# RGBDisplayDriver.net
KiCad netlist of a schematic drawn in EAGLE
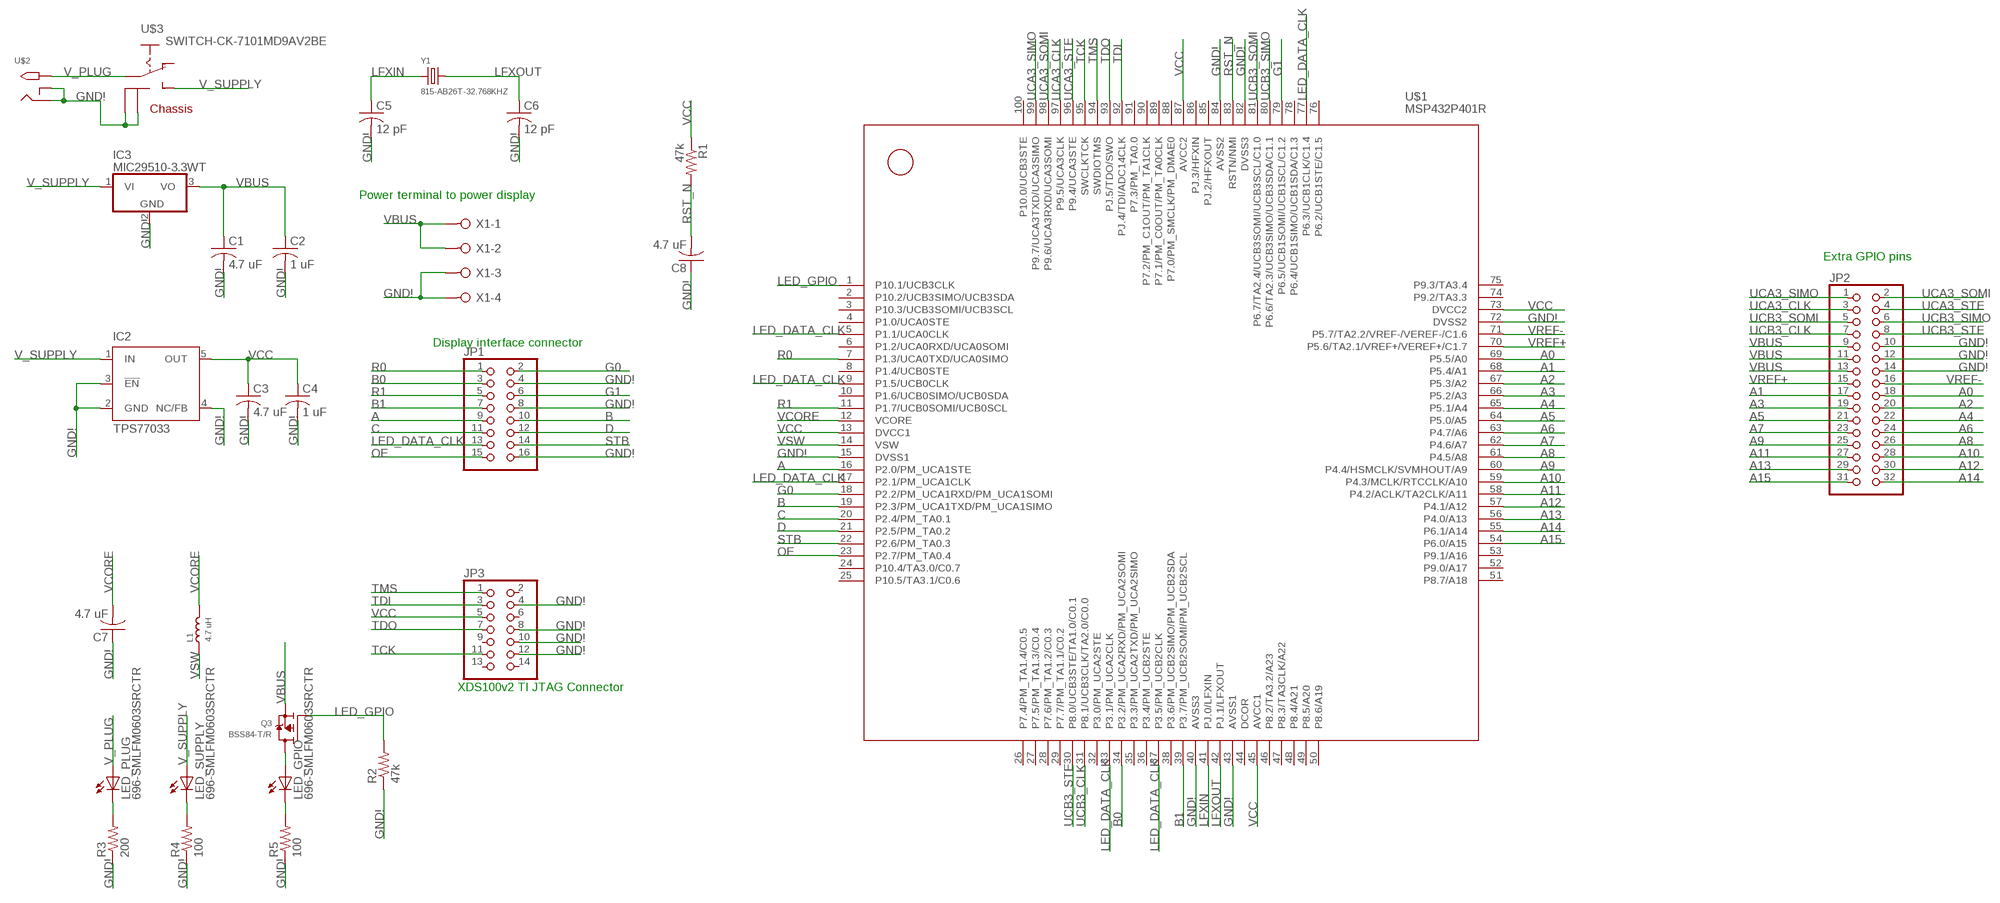
[diagram p0: schematic, sheet 1]

(export (version "E")
  (design (tool "Eeschema 10.0.6"))
  (components
    (comp (ref "C1")
      (value "4.7 uF")
      (footprint "eagle-import:C0603")
      (libsource (lib "eagle-import") (part "C-USC0603"))
    )
    (comp (ref "C2")
      (value "1 uF")
      (footprint "eagle-import:C0603")
      (libsource (lib "eagle-import") (part "C-USC0603"))
    )
    (comp (ref "C3")
      (value "4.7 uF")
      (footprint "eagle-import:C0603")
      (libsource (lib "eagle-import") (part "C-USC0603"))
    )
    (comp (ref "C4")
      (value "1 uF")
      (footprint "eagle-import:C0603")
      (libsource (lib "eagle-import") (part "C-USC0603"))
    )
    (comp (ref "C5")
      (value "12 pF")
      (footprint "eagle-import:C0603")
      (libsource (lib "eagle-import") (part "C-USC0603"))
    )
    (comp (ref "C6")
      (value "12 pF")
      (footprint "eagle-import:C0603")
      (libsource (lib "eagle-import") (part "C-USC0603"))
    )
    (comp (ref "C7")
      (value "4.7 uF")
      (footprint "eagle-import:C0603")
      (libsource (lib "eagle-import") (part "C-USC0603"))
    )
    (comp (ref "C8")
      (value "4.7 uF")
      (footprint "eagle-import:C0603")
      (libsource (lib "eagle-import") (part "C-USC0603"))
    )
    (comp (ref "IC2")
      (value "TPS77033")
      (footprint "eagle-import:SOT23-DBV")
      (fields (field (name "MF") "TEXAS INSTRUMENTS") (field (name "MPN") "TPS77033DBVT"))
      (libsource (lib "eagle-import") (part "TPS77033"))
    )
    (comp (ref "IC3")
      (value "MIC29510-3.3WT")
      (footprint "eagle-import:TO220V")
      (libsource (lib "eagle-import") (part "78TV05"))
    )
    (comp (ref "JP1")
      (value "PINHD-2X8")
      (footprint "eagle-import:2X08")
      (libsource (lib "eagle-import") (part "PINHD-2X8"))
    )
    (comp (ref "JP2")
      (value "PINHD-2X16")
      (footprint "eagle-import:2X16")
      (libsource (lib "eagle-import") (part "PINHD-2X16"))
    )
    (comp (ref "JP3")
      (value "PINHD-2X7")
      (footprint "eagle-import:2X07")
      (libsource (lib "eagle-import") (part "PINHD-2X7"))
    )
    (comp (ref "L1")
      (value "4.7 uH")
      (footprint "eagle-import:L0603")
      (fields (field (name "MPN") "BLM18AG121SN1D"))
      (libsource (lib "eagle-import") (part "SMD-FERRITE-CHIP-120-OHM-500MA(0603)"))
    )
    (comp (ref "LED_GPIO")
      (value "696-SMLFM0603SRCTR")
      (footprint "eagle-import:CHIPLED_0603")
      (libsource (lib "eagle-import") (part "LEDCHIPLED_0603"))
    )
    (comp (ref "LED_PLUG")
      (value "696-SMLFM0603SRCTR")
      (footprint "eagle-import:CHIPLED_0603")
      (libsource (lib "eagle-import") (part "LEDCHIPLED_0603"))
    )
    (comp (ref "LED_SUPPLY")
      (value "696-SMLFM0603SRCTR")
      (footprint "eagle-import:CHIPLED_0603")
      (libsource (lib "eagle-import") (part "LEDCHIPLED_0603"))
    )
    (comp (ref "Q3")
      (value "BSS84-T/R")
      (footprint "eagle-import:SOT23-WIDE")
      (libsource (lib "eagle-import") (part "MOSFET-PWIDE"))
    )
    (comp (ref "R1")
      (value "47k")
      (footprint "eagle-import:R0603")
      (libsource (lib "eagle-import") (part "R-US_R0603"))
    )
    (comp (ref "R2")
      (value "47k")
      (footprint "eagle-import:R0603")
      (libsource (lib "eagle-import") (part "R-US_R0603"))
    )
    (comp (ref "R3")
      (value "200")
      (footprint "eagle-import:R0603")
      (libsource (lib "eagle-import") (part "R-US_R0603"))
    )
    (comp (ref "R4")
      (value "100")
      (footprint "eagle-import:R0603")
      (libsource (lib "eagle-import") (part "R-US_R0603"))
    )
    (comp (ref "R5")
      (value "100")
      (footprint "eagle-import:R0603")
      (libsource (lib "eagle-import") (part "R-US_R0603"))
    )
    (comp (ref "U$1")
      (value "MSP432P401R")
      (footprint "eagle-import:LQFP100")
      (libsource (lib "eagle-import") (part "MSP432P401XPZ"))
    )
    (comp (ref "U$2")
      (value "2.1MMJACKTHM")
      (footprint "eagle-import:PJ-102A")
      (libsource (lib "eagle-import") (part "2.1MMJACKTHM"))
    )
    (comp (ref "U$3")
      (value "SWITCH-CK-7101MD9AV2BE")
      (footprint "eagle-import:SWITCH-CK-7101MD9AV2BE")
      (libsource (lib "eagle-import") (part "SWITCH-CK-7101MD9AV2BE"))
    )
    (comp (ref "X1")
      (value "W237-04P")
      (footprint "eagle-import:W237-4P")
      (libsource (lib "eagle-import") (part "W237-04P"))
    )
    (comp (ref "Y1")
      (value "815-AB26T-32.768KHZ")
      (footprint "eagle-import:CRYSTAL_CYL_2X6MM_SMT")
      (libsource (lib "eagle-import") (part "CRYSTAL32.768"))
    )
  )
  (nets
    (net (code "1") (name "/A") (class "Default")
      (node (ref "JP1") (pin "9") (pinfunction "9_9") (pintype "passive"))
      (node (ref "U$1") (pin "16") (pinfunction "P2.0/PM_UCA1STE_16") (pintype "bidirectional"))
    )
    (net (code "2") (name "/A0") (class "Default")
      (node (ref "JP2") (pin "18") (pinfunction "18_18") (pintype "passive"))
      (node (ref "U$1") (pin "69") (pinfunction "P5.5/A0_69") (pintype "bidirectional"))
    )
    (net (code "3") (name "/A1") (class "Default")
      (node (ref "JP2") (pin "17") (pinfunction "17_17") (pintype "passive"))
      (node (ref "U$1") (pin "68") (pinfunction "P5.4/A1_68") (pintype "bidirectional"))
    )
    (net (code "4") (name "/A2") (class "Default")
      (node (ref "JP2") (pin "20") (pinfunction "20_20") (pintype "passive"))
      (node (ref "U$1") (pin "67") (pinfunction "P5.3/A2_67") (pintype "bidirectional"))
    )
    (net (code "5") (name "/A3") (class "Default")
      (node (ref "JP2") (pin "19") (pinfunction "19_19") (pintype "passive"))
      (node (ref "U$1") (pin "66") (pinfunction "P5.2/A3_66") (pintype "bidirectional"))
    )
    (net (code "6") (name "/A4") (class "Default")
      (node (ref "JP2") (pin "22") (pinfunction "22_22") (pintype "passive"))
      (node (ref "U$1") (pin "65") (pinfunction "P5.1/A4_65") (pintype "bidirectional"))
    )
    (net (code "7") (name "/A5") (class "Default")
      (node (ref "JP2") (pin "21") (pinfunction "21_21") (pintype "passive"))
      (node (ref "U$1") (pin "64") (pinfunction "P5.0/A5_64") (pintype "bidirectional"))
    )
    (net (code "8") (name "/A6") (class "Default")
      (node (ref "JP2") (pin "24") (pinfunction "24_24") (pintype "passive"))
      (node (ref "U$1") (pin "63") (pinfunction "P4.7/A6_63") (pintype "bidirectional"))
    )
    (net (code "9") (name "/A7") (class "Default")
      (node (ref "JP2") (pin "23") (pinfunction "23_23") (pintype "passive"))
      (node (ref "U$1") (pin "62") (pinfunction "P4.6/A7_62") (pintype "bidirectional"))
    )
    (net (code "10") (name "/A8") (class "Default")
      (node (ref "JP2") (pin "26") (pinfunction "26_26") (pintype "passive"))
      (node (ref "U$1") (pin "61") (pinfunction "P4.5/A8_61") (pintype "bidirectional"))
    )
    (net (code "11") (name "/A9") (class "Default")
      (node (ref "JP2") (pin "25") (pinfunction "25_25") (pintype "passive"))
      (node (ref "U$1") (pin "60") (pinfunction "P4.4/HSMCLK/SVMHOUT/A9_60") (pintype "bidirectional"))
    )
    (net (code "12") (name "/A10") (class "Default")
      (node (ref "JP2") (pin "28") (pinfunction "28_28") (pintype "passive"))
      (node (ref "U$1") (pin "59") (pinfunction "P4.3/MCLK/RTCCLK/A10_59") (pintype "bidirectional"))
    )
    (net (code "13") (name "/A11") (class "Default")
      (node (ref "JP2") (pin "27") (pinfunction "27_27") (pintype "passive"))
      (node (ref "U$1") (pin "58") (pinfunction "P4.2/ACLK/TA2CLK/A11_58") (pintype "bidirectional"))
    )
    (net (code "14") (name "/A12") (class "Default")
      (node (ref "JP2") (pin "30") (pinfunction "30_30") (pintype "passive"))
      (node (ref "U$1") (pin "57") (pinfunction "P4.1/A12_57") (pintype "bidirectional"))
    )
    (net (code "15") (name "/A13") (class "Default")
      (node (ref "JP2") (pin "29") (pinfunction "29_29") (pintype "passive"))
      (node (ref "U$1") (pin "56") (pinfunction "P4.0/A13_56") (pintype "bidirectional"))
    )
    (net (code "16") (name "/A14") (class "Default")
      (node (ref "JP2") (pin "32") (pinfunction "32_32") (pintype "passive"))
      (node (ref "U$1") (pin "55") (pinfunction "P6.1/A14_55") (pintype "bidirectional"))
    )
    (net (code "17") (name "/A15") (class "Default")
      (node (ref "JP2") (pin "31") (pinfunction "31_31") (pintype "passive"))
      (node (ref "U$1") (pin "54") (pinfunction "P6.0/A15_54") (pintype "bidirectional"))
    )
    (net (code "18") (name "/B") (class "Default")
      (node (ref "JP1") (pin "10") (pinfunction "10_10") (pintype "passive"))
      (node (ref "U$1") (pin "19") (pinfunction "P2.3/PM_UCA1TXD/PM_UCA1SIMO_19") (pintype "bidirectional"))
    )
    (net (code "19") (name "/B0") (class "Default")
      (node (ref "JP1") (pin "3") (pinfunction "3_3") (pintype "passive"))
      (node (ref "U$1") (pin "34") (pinfunction "P3.2/PM_UCA2RXD/PM_UCA2SOMI_34") (pintype "bidirectional"))
    )
    (net (code "20") (name "/B1") (class "Default")
      (node (ref "JP1") (pin "7") (pinfunction "7_7") (pintype "passive"))
      (node (ref "U$1") (pin "39") (pinfunction "P3.7/PM_UCB2SOMI/PM_UCB2SCL_39") (pintype "bidirectional"))
    )
    (net (code "21") (name "/C") (class "Default")
      (node (ref "JP1") (pin "11") (pinfunction "11_11") (pintype "passive"))
      (node (ref "U$1") (pin "20") (pinfunction "P2.4/PM_TA0.1_20") (pintype "bidirectional"))
    )
    (net (code "22") (name "/D") (class "Default")
      (node (ref "JP1") (pin "12") (pinfunction "12_12") (pintype "passive"))
      (node (ref "U$1") (pin "21") (pinfunction "P2.5/PM_TA0.2_21") (pintype "bidirectional"))
    )
    (net (code "23") (name "/G0") (class "Default")
      (node (ref "JP1") (pin "2") (pinfunction "2_2") (pintype "passive"))
      (node (ref "U$1") (pin "18") (pinfunction "P2.2/PM_UCA1RXD/PM_UCA1SOMI_18") (pintype "bidirectional"))
    )
    (net (code "24") (name "/G1") (class "Default")
      (node (ref "JP1") (pin "6") (pinfunction "6_6") (pintype "passive"))
      (node (ref "U$1") (pin "79") (pinfunction "P6.5/UCB1SOMI/UCB1SCL/C1.2_79") (pintype "bidirectional"))
    )
    (net (code "25") (name "/GND~{}") (class "Default")
      (node (ref "C1") (pin "2") (pinfunction "2_2") (pintype "passive"))
      (node (ref "C2") (pin "2") (pinfunction "2_2") (pintype "passive"))
      (node (ref "C3") (pin "2") (pinfunction "2_2") (pintype "passive"))
      (node (ref "C4") (pin "2") (pinfunction "2_2") (pintype "passive"))
      (node (ref "C5") (pin "2") (pinfunction "2_2") (pintype "passive"))
      (node (ref "C6") (pin "2") (pinfunction "2_2") (pintype "passive"))
      (node (ref "C7") (pin "1") (pinfunction "1_1") (pintype "passive"))
      (node (ref "C8") (pin "1") (pinfunction "1_1") (pintype "passive"))
      (node (ref "IC2") (pin "2") (pinfunction "GND_2") (pintype "power_in"))
      (node (ref "IC2") (pin "3") (pinfunction "~{EN}_3") (pintype "input"))
      (node (ref "IC2") (pin "4") (pinfunction "NC/FB_4") (pintype "passive"))
      (node (ref "IC3") (pin "2") (pinfunction "GND_2") (pintype "passive"))
      (node (ref "JP1") (pin "16") (pinfunction "16_16") (pintype "passive"))
      (node (ref "JP1") (pin "4") (pinfunction "4_4") (pintype "passive"))
      (node (ref "JP1") (pin "8") (pinfunction "8_8") (pintype "passive"))
      (node (ref "JP2") (pin "10") (pinfunction "10_10") (pintype "passive"))
      (node (ref "JP2") (pin "12") (pinfunction "12_12") (pintype "passive"))
      (node (ref "JP2") (pin "14") (pinfunction "14_14") (pintype "passive"))
      (node (ref "JP3") (pin "10") (pinfunction "10_10") (pintype "passive"))
      (node (ref "JP3") (pin "12") (pinfunction "12_12") (pintype "passive"))
      (node (ref "JP3") (pin "4") (pinfunction "4_4") (pintype "passive"))
      (node (ref "JP3") (pin "8") (pinfunction "8_8") (pintype "passive"))
      (node (ref "R2") (pin "1") (pinfunction "1_1") (pintype "passive"))
      (node (ref "R3") (pin "1") (pinfunction "1_1") (pintype "passive"))
      (node (ref "R4") (pin "1") (pinfunction "1_1") (pintype "passive"))
      (node (ref "R5") (pin "1") (pinfunction "1_1") (pintype "passive"))
      (node (ref "U$1") (pin "15") (pinfunction "DVSS1_15") (pintype "bidirectional"))
      (node (ref "U$1") (pin "40") (pinfunction "AVSS3_40") (pintype "bidirectional"))
      (node (ref "U$1") (pin "43") (pinfunction "AVSS1_43") (pintype "bidirectional"))
      (node (ref "U$1") (pin "72") (pinfunction "DVSS2_72") (pintype "bidirectional"))
      (node (ref "U$1") (pin "82") (pinfunction "DVSS3_82") (pintype "bidirectional"))
      (node (ref "U$1") (pin "84") (pinfunction "AVSS2_84") (pintype "bidirectional"))
      (node (ref "U$2") (pin "RING") (pinfunction "RING_RING") (pintype "bidirectional"))
      (node (ref "U$2") (pin "RING_SW") (pinfunction "RING_SW_RING_SW") (pintype "bidirectional"))
      (node (ref "U$3") (pin "P$4") (pinfunction "P$4_P$4") (pintype "bidirectional"))
      (node (ref "U$3") (pin "P$5") (pinfunction "P$5_P$5") (pintype "bidirectional"))
      (node (ref "X1") (pin "3") (pinfunction "KL_3") (pintype "passive"))
      (node (ref "X1") (pin "4") (pinfunction "KL_4") (pintype "passive"))
    )
    (net (code "26") (name "/LED_DATA_CLK") (class "Default")
      (node (ref "JP1") (pin "13") (pinfunction "13_13") (pintype "passive"))
      (node (ref "U$1") (pin "17") (pinfunction "P2.1/PM_UCA1CLK_17") (pintype "bidirectional"))
      (node (ref "U$1") (pin "33") (pinfunction "P3.1/PM_UCA2CLK_33") (pintype "bidirectional"))
      (node (ref "U$1") (pin "37") (pinfunction "P3.5/PM_UCB2CLK_37") (pintype "bidirectional"))
      (node (ref "U$1") (pin "5") (pinfunction "P1.1/UCA0CLK_5") (pintype "bidirectional"))
      (node (ref "U$1") (pin "77") (pinfunction "P6.3/UCB1CLK/C1.4_77") (pintype "bidirectional"))
      (node (ref "U$1") (pin "9") (pinfunction "P1.5/UCB0CLK_9") (pintype "bidirectional"))
    )
    (net (code "27") (name "/LED_GPIO") (class "Default")
      (node (ref "Q3") (pin "1") (pinfunction "G_1") (pintype "passive"))
      (node (ref "R2") (pin "2") (pinfunction "2_2") (pintype "passive"))
      (node (ref "U$1") (pin "1") (pinfunction "P10.1/UCB3CLK_1") (pintype "bidirectional"))
    )
    (net (code "28") (name "/LFXIN") (class "Default")
      (node (ref "C5") (pin "1") (pinfunction "1_1") (pintype "passive"))
      (node (ref "U$1") (pin "41") (pinfunction "PJ.0/LFXIN_41") (pintype "bidirectional"))
      (node (ref "Y1") (pin "1") (pinfunction "1_1") (pintype "passive"))
    )
    (net (code "29") (name "/LFXOUT") (class "Default")
      (node (ref "C6") (pin "1") (pinfunction "1_1") (pintype "passive"))
      (node (ref "U$1") (pin "42") (pinfunction "PJ.1/LFXOUT_42") (pintype "bidirectional"))
      (node (ref "Y1") (pin "2") (pinfunction "2_2") (pintype "passive"))
    )
    (net (code "30") (name "/OE") (class "Default")
      (node (ref "JP1") (pin "15") (pinfunction "15_15") (pintype "passive"))
      (node (ref "U$1") (pin "23") (pinfunction "P2.7/PM_TA0.4_23") (pintype "bidirectional"))
    )
    (net (code "31") (name "/R0") (class "Default")
      (node (ref "JP1") (pin "1") (pinfunction "1_1") (pintype "passive"))
      (node (ref "U$1") (pin "7") (pinfunction "P1.3/UCA0TXD/UCA0SIMO_7") (pintype "bidirectional"))
    )
    (net (code "32") (name "/R1") (class "Default")
      (node (ref "JP1") (pin "5") (pinfunction "5_5") (pintype "passive"))
      (node (ref "U$1") (pin "11") (pinfunction "P1.7/UCB0SOMI/UCB0SCL_11") (pintype "bidirectional"))
    )
    (net (code "33") (name "/RST_N") (class "Default")
      (node (ref "C8") (pin "2") (pinfunction "2_2") (pintype "passive"))
      (node (ref "R1") (pin "2") (pinfunction "2_2") (pintype "passive"))
      (node (ref "U$1") (pin "83") (pinfunction "RSTN/NMI_83") (pintype "bidirectional"))
    )
    (net (code "34") (name "/STB") (class "Default")
      (node (ref "JP1") (pin "14") (pinfunction "14_14") (pintype "passive"))
      (node (ref "U$1") (pin "22") (pinfunction "P2.6/PM_TA0.3_22") (pintype "bidirectional"))
    )
    (net (code "35") (name "/TCK") (class "Default")
      (node (ref "JP3") (pin "11") (pinfunction "11_11") (pintype "passive"))
      (node (ref "U$1") (pin "95") (pinfunction "SWCLKTCK_95") (pintype "bidirectional"))
    )
    (net (code "36") (name "/TDI") (class "Default")
      (node (ref "JP3") (pin "3") (pinfunction "3_3") (pintype "passive"))
      (node (ref "U$1") (pin "92") (pinfunction "PJ.4/TDI/ADC14CLK_92") (pintype "bidirectional"))
    )
    (net (code "37") (name "/TDO") (class "Default")
      (node (ref "JP3") (pin "7") (pinfunction "7_7") (pintype "passive"))
      (node (ref "U$1") (pin "93") (pinfunction "PJ.5/TDO/SWO_93") (pintype "bidirectional"))
    )
    (net (code "38") (name "/TMS") (class "Default")
      (node (ref "JP3") (pin "1") (pinfunction "1_1") (pintype "passive"))
      (node (ref "U$1") (pin "94") (pinfunction "SWDIOTMS_94") (pintype "bidirectional"))
    )
    (net (code "39") (name "/UCA3_CLK") (class "Default")
      (node (ref "JP2") (pin "3") (pinfunction "3_3") (pintype "passive"))
      (node (ref "U$1") (pin "97") (pinfunction "P9.5/UCA3CLK_97") (pintype "bidirectional"))
    )
    (net (code "40") (name "/UCA3_SIMO") (class "Default")
      (node (ref "JP2") (pin "1") (pinfunction "1_1") (pintype "passive"))
      (node (ref "U$1") (pin "99") (pinfunction "P9.7/UCA3TXD/UCA3SIMO_99") (pintype "bidirectional"))
    )
    (net (code "41") (name "/UCA3_SOMI") (class "Default")
      (node (ref "JP2") (pin "2") (pinfunction "2_2") (pintype "passive"))
      (node (ref "U$1") (pin "98") (pinfunction "P9.6/UCA3RXD/UCA3SOMI_98") (pintype "bidirectional"))
    )
    (net (code "42") (name "/UCA3_STE") (class "Default")
      (node (ref "JP2") (pin "4") (pinfunction "4_4") (pintype "passive"))
      (node (ref "U$1") (pin "96") (pinfunction "P9.4/UCA3STE_96") (pintype "bidirectional"))
    )
    (net (code "43") (name "/UCB3_CLK") (class "Default")
      (node (ref "JP2") (pin "7") (pinfunction "7_7") (pintype "passive"))
      (node (ref "U$1") (pin "31") (pinfunction "P8.1/UCB3CLK/TA2.0/C0.0_31") (pintype "bidirectional"))
    )
    (net (code "44") (name "/UCB3_SIMO") (class "Default")
      (node (ref "JP2") (pin "6") (pinfunction "6_6") (pintype "passive"))
      (node (ref "U$1") (pin "80") (pinfunction "P6.6/TA2.3/UCB3SIMO/UCB3SDA/C1.1_80") (pintype "bidirectional"))
    )
    (net (code "45") (name "/UCB3_SOMI") (class "Default")
      (node (ref "JP2") (pin "5") (pinfunction "5_5") (pintype "passive"))
      (node (ref "U$1") (pin "81") (pinfunction "P6.7/TA2.4/UCB3SOMI/UCB3SCL/C1.0_81") (pintype "bidirectional"))
    )
    (net (code "46") (name "/UCB3_STE") (class "Default")
      (node (ref "JP2") (pin "8") (pinfunction "8_8") (pintype "passive"))
      (node (ref "U$1") (pin "30") (pinfunction "P8.0/UCB3STE/TA1.0/C0.1_30") (pintype "bidirectional"))
    )
    (net (code "47") (name "/VBUS") (class "Default")
      (node (ref "C1") (pin "1") (pinfunction "1_1") (pintype "passive"))
      (node (ref "C2") (pin "1") (pinfunction "1_1") (pintype "passive"))
      (node (ref "IC3") (pin "3") (pinfunction "VO_3") (pintype "passive"))
      (node (ref "JP2") (pin "11") (pinfunction "11_11") (pintype "passive"))
      (node (ref "JP2") (pin "13") (pinfunction "13_13") (pintype "passive"))
      (node (ref "JP2") (pin "9") (pinfunction "9_9") (pintype "passive"))
      (node (ref "Q3") (pin "2") (pinfunction "S_2") (pintype "passive"))
      (node (ref "X1") (pin "1") (pinfunction "KL_1") (pintype "passive"))
      (node (ref "X1") (pin "2") (pinfunction "KL_2") (pintype "passive"))
    )
    (net (code "48") (name "/VCC") (class "Default")
      (node (ref "C3") (pin "1") (pinfunction "1_1") (pintype "passive"))
      (node (ref "C4") (pin "1") (pinfunction "1_1") (pintype "passive"))
      (node (ref "IC2") (pin "5") (pinfunction "OUT_5") (pintype "passive"))
      (node (ref "JP3") (pin "5") (pinfunction "5_5") (pintype "passive"))
      (node (ref "R1") (pin "1") (pinfunction "1_1") (pintype "passive"))
      (node (ref "U$1") (pin "13") (pinfunction "DVCC1_13") (pintype "bidirectional"))
      (node (ref "U$1") (pin "45") (pinfunction "AVCC1_45") (pintype "bidirectional"))
      (node (ref "U$1") (pin "73") (pinfunction "DVCC2_73") (pintype "bidirectional"))
      (node (ref "U$1") (pin "87") (pinfunction "AVCC2_87") (pintype "bidirectional"))
    )
    (net (code "49") (name "/VCORE") (class "Default")
      (node (ref "C7") (pin "2") (pinfunction "2_2") (pintype "passive"))
      (node (ref "L1") (pin "2") (pinfunction "2_2") (pintype "passive"))
      (node (ref "U$1") (pin "12") (pinfunction "VCORE_12") (pintype "bidirectional"))
    )
    (net (code "50") (name "/VREF+") (class "Default")
      (node (ref "JP2") (pin "15") (pinfunction "15_15") (pintype "passive"))
      (node (ref "U$1") (pin "70") (pinfunction "P5.6/TA2.1/VREF+/VEREF+/C1.7_70") (pintype "bidirectional"))
    )
    (net (code "51") (name "/VREF-") (class "Default")
      (node (ref "JP2") (pin "16") (pinfunction "16_16") (pintype "passive"))
      (node (ref "U$1") (pin "71") (pinfunction "P5.7/TA2.2/VREF-/VEREF-/C1.6_71") (pintype "bidirectional"))
    )
    (net (code "52") (name "/VSW") (class "Default")
      (node (ref "L1") (pin "1") (pinfunction "1_1") (pintype "passive"))
      (node (ref "U$1") (pin "14") (pinfunction "VSW_14") (pintype "bidirectional"))
    )
    (net (code "53") (name "/V_PLUG") (class "Default")
      (node (ref "LED_PLUG") (pin "A") (pinfunction "A_A") (pintype "passive"))
      (node (ref "U$2") (pin "TIP") (pinfunction "TIP_TIP") (pintype "bidirectional"))
      (node (ref "U$3") (pin "P$2") (pinfunction "P$2_P$2") (pintype "passive"))
    )
    (net (code "54") (name "/V_SUPPLY") (class "Default")
      (node (ref "IC2") (pin "1") (pinfunction "IN_1") (pintype "input"))
      (node (ref "IC3") (pin "1") (pinfunction "VI_1") (pintype "input"))
      (node (ref "LED_SUPPLY") (pin "A") (pinfunction "A_A") (pintype "passive"))
      (node (ref "U$3") (pin "P$1") (pinfunction "P$1_P$1") (pintype "passive"))
    )
    (net (code "55") (name "Net-(LED_GPIO-PadC)") (class "Default")
      (node (ref "LED_GPIO") (pin "C") (pinfunction "C_C") (pintype "passive"))
      (node (ref "R5") (pin "2") (pinfunction "2_2") (pintype "passive"))
    )
    (net (code "56") (name "Net-(LED_PLUG-PadC)") (class "Default")
      (node (ref "LED_PLUG") (pin "C") (pinfunction "C_C") (pintype "passive"))
      (node (ref "R3") (pin "2") (pinfunction "2_2") (pintype "passive"))
    )
    (net (code "57") (name "Net-(LED_SUPPLY-PadC)") (class "Default")
      (node (ref "LED_SUPPLY") (pin "C") (pinfunction "C_C") (pintype "passive"))
      (node (ref "R4") (pin "2") (pinfunction "2_2") (pintype "passive"))
    )
    (net (code "58") (name "Net-(Q3-D)") (class "Default")
      (node (ref "LED_GPIO") (pin "A") (pinfunction "A_A") (pintype "passive"))
      (node (ref "Q3") (pin "3") (pinfunction "D_3") (pintype "passive"))
    )
    (net (code "59") (name "unconnected-(JP3-Pad2)") (class "Default")
      (node (ref "JP3") (pin "2") (pinfunction "2_2") (pintype "passive"))
    )
    (net (code "60") (name "unconnected-(JP3-Pad6)") (class "Default")
      (node (ref "JP3") (pin "6") (pinfunction "6_6") (pintype "passive"))
    )
    (net (code "61") (name "unconnected-(JP3-Pad9)") (class "Default")
      (node (ref "JP3") (pin "9") (pinfunction "9_9") (pintype "passive"))
    )
    (net (code "62") (name "unconnected-(JP3-Pad13)") (class "Default")
      (node (ref "JP3") (pin "13") (pinfunction "13_13") (pintype "passive"))
    )
    (net (code "63") (name "unconnected-(JP3-Pad14)") (class "Default")
      (node (ref "JP3") (pin "14") (pinfunction "14_14") (pintype "passive"))
    )
    (net (code "64") (name "unconnected-(U$1-DCOR-Pad44)") (class "Default")
      (node (ref "U$1") (pin "44") (pinfunction "DCOR_44") (pintype "bidirectional"))
    )
    (net (code "65") (name "unconnected-(U$1-P1.0{slash}UCA0STE-Pad4)") (class "Default")
      (node (ref "U$1") (pin "4") (pinfunction "P1.0/UCA0STE_4") (pintype "bidirectional"))
    )
    (net (code "66") (name "unconnected-(U$1-P1.2{slash}UCA0RXD{slash}UCA0SOMI-Pad6)") (class "Default")
      (node (ref "U$1") (pin "6") (pinfunction "P1.2/UCA0RXD/UCA0SOMI_6") (pintype "bidirectional"))
    )
    (net (code "67") (name "unconnected-(U$1-P1.4{slash}UCB0STE-Pad8)") (class "Default")
      (node (ref "U$1") (pin "8") (pinfunction "P1.4/UCB0STE_8") (pintype "bidirectional"))
    )
    (net (code "68") (name "unconnected-(U$1-P1.6{slash}UCB0SIMO{slash}UCB0SDA-Pad10)") (class "Default")
      (node (ref "U$1") (pin "10") (pinfunction "P1.6/UCB0SIMO/UCB0SDA_10") (pintype "bidirectional"))
    )
    (net (code "69") (name "unconnected-(U$1-P3.0{slash}PM_UCA2STE-Pad32)") (class "Default")
      (node (ref "U$1") (pin "32") (pinfunction "P3.0/PM_UCA2STE_32") (pintype "bidirectional"))
    )
    (net (code "70") (name "unconnected-(U$1-P3.3{slash}PM_UCA2TXD{slash}PM_UCA2SIMO-Pad35)") (class "Default")
      (node (ref "U$1") (pin "35") (pinfunction "P3.3/PM_UCA2TXD/PM_UCA2SIMO_35") (pintype "bidirectional"))
    )
    (net (code "71") (name "unconnected-(U$1-P3.4{slash}PM_UCB2STE-Pad36)") (class "Default")
      (node (ref "U$1") (pin "36") (pinfunction "P3.4/PM_UCB2STE_36") (pintype "bidirectional"))
    )
    (net (code "72") (name "unconnected-(U$1-P3.6{slash}PM_UCB2SIMO{slash}PM_UCB2SDA-Pad38)") (class "Default")
      (node (ref "U$1") (pin "38") (pinfunction "P3.6/PM_UCB2SIMO/PM_UCB2SDA_38") (pintype "bidirectional"))
    )
    (net (code "73") (name "unconnected-(U$1-P6.2{slash}UCB1STE{slash}C1.5-Pad76)") (class "Default")
      (node (ref "U$1") (pin "76") (pinfunction "P6.2/UCB1STE/C1.5_76") (pintype "bidirectional"))
    )
    (net (code "74") (name "unconnected-(U$1-P6.4{slash}UCB1SIMO{slash}UCB1SDA{slash}C1.3-Pad78)") (class "Default")
      (node (ref "U$1") (pin "78") (pinfunction "P6.4/UCB1SIMO/UCB1SDA/C1.3_78") (pintype "bidirectional"))
    )
    (net (code "75") (name "unconnected-(U$1-P7.0{slash}PM_SMCLK{slash}PM_DMAE0-Pad88)") (class "Default")
      (node (ref "U$1") (pin "88") (pinfunction "P7.0/PM_SMCLK/PM_DMAE0_88") (pintype "bidirectional"))
    )
    (net (code "76") (name "unconnected-(U$1-P7.1{slash}PM_C0OUT{slash}PM_TA0CLK-Pad89)") (class "Default")
      (node (ref "U$1") (pin "89") (pinfunction "P7.1/PM_C0OUT/PM_TA0CLK_89") (pintype "bidirectional"))
    )
    (net (code "77") (name "unconnected-(U$1-P7.2{slash}PM_C1OUT{slash}PM_TA1CLK-Pad90)") (class "Default")
      (node (ref "U$1") (pin "90") (pinfunction "P7.2/PM_C1OUT/PM_TA1CLK_90") (pintype "bidirectional"))
    )
    (net (code "78") (name "unconnected-(U$1-P7.3{slash}PM_TA0.0-Pad91)") (class "Default")
      (node (ref "U$1") (pin "91") (pinfunction "P7.3/PM_TA0.0_91") (pintype "bidirectional"))
    )
    (net (code "79") (name "unconnected-(U$1-P7.4{slash}PM_TA1.4{slash}C0.5-Pad26)") (class "Default")
      (node (ref "U$1") (pin "26") (pinfunction "P7.4/PM_TA1.4/C0.5_26") (pintype "bidirectional"))
    )
    (net (code "80") (name "unconnected-(U$1-P7.5{slash}PM_TA1.3{slash}C0.4-Pad27)") (class "Default")
      (node (ref "U$1") (pin "27") (pinfunction "P7.5/PM_TA1.3/C0.4_27") (pintype "bidirectional"))
    )
    (net (code "81") (name "unconnected-(U$1-P7.6{slash}PM_TA1.2{slash}C0.3-Pad28)") (class "Default")
      (node (ref "U$1") (pin "28") (pinfunction "P7.6/PM_TA1.2/C0.3_28") (pintype "bidirectional"))
    )
    (net (code "82") (name "unconnected-(U$1-P7.7{slash}PM_TA1.1{slash}C0.2-Pad29)") (class "Default")
      (node (ref "U$1") (pin "29") (pinfunction "P7.7/PM_TA1.1/C0.2_29") (pintype "bidirectional"))
    )
    (net (code "83") (name "unconnected-(U$1-P8.2{slash}TA3.2{slash}A23-Pad46)") (class "Default")
      (node (ref "U$1") (pin "46") (pinfunction "P8.2/TA3.2/A23_46") (pintype "bidirectional"))
    )
    (net (code "84") (name "unconnected-(U$1-P8.3{slash}TA3CLK{slash}A22-Pad47)") (class "Default")
      (node (ref "U$1") (pin "47") (pinfunction "P8.3/TA3CLK/A22_47") (pintype "bidirectional"))
    )
    (net (code "85") (name "unconnected-(U$1-P8.4{slash}A21-Pad48)") (class "Default")
      (node (ref "U$1") (pin "48") (pinfunction "P8.4/A21_48") (pintype "bidirectional"))
    )
    (net (code "86") (name "unconnected-(U$1-P8.5{slash}A20-Pad49)") (class "Default")
      (node (ref "U$1") (pin "49") (pinfunction "P8.5/A20_49") (pintype "bidirectional"))
    )
    (net (code "87") (name "unconnected-(U$1-P8.6{slash}A19-Pad50)") (class "Default")
      (node (ref "U$1") (pin "50") (pinfunction "P8.6/A19_50") (pintype "bidirectional"))
    )
    (net (code "88") (name "unconnected-(U$1-P8.7{slash}A18-Pad51)") (class "Default")
      (node (ref "U$1") (pin "51") (pinfunction "P8.7/A18_51") (pintype "bidirectional"))
    )
    (net (code "89") (name "unconnected-(U$1-P9.0{slash}A17-Pad52)") (class "Default")
      (node (ref "U$1") (pin "52") (pinfunction "P9.0/A17_52") (pintype "bidirectional"))
    )
    (net (code "90") (name "unconnected-(U$1-P9.1{slash}A16-Pad53)") (class "Default")
      (node (ref "U$1") (pin "53") (pinfunction "P9.1/A16_53") (pintype "bidirectional"))
    )
    (net (code "91") (name "unconnected-(U$1-P9.2{slash}TA3.3-Pad74)") (class "Default")
      (node (ref "U$1") (pin "74") (pinfunction "P9.2/TA3.3_74") (pintype "bidirectional"))
    )
    (net (code "92") (name "unconnected-(U$1-P9.3{slash}TA3.4-Pad75)") (class "Default")
      (node (ref "U$1") (pin "75") (pinfunction "P9.3/TA3.4_75") (pintype "bidirectional"))
    )
    (net (code "93") (name "unconnected-(U$1-P10.0{slash}UCB3STE-Pad100)") (class "Default")
      (node (ref "U$1") (pin "100") (pinfunction "P10.0/UCB3STE_100") (pintype "bidirectional"))
    )
    (net (code "94") (name "unconnected-(U$1-P10.2{slash}UCB3SIMO{slash}UCB3SDA-Pad2)") (class "Default")
      (node (ref "U$1") (pin "2") (pinfunction "P10.2/UCB3SIMO/UCB3SDA_2") (pintype "bidirectional"))
    )
    (net (code "95") (name "unconnected-(U$1-P10.3{slash}UCB3SOMI{slash}UCB3SCL-Pad3)") (class "Default")
      (node (ref "U$1") (pin "3") (pinfunction "P10.3/UCB3SOMI/UCB3SCL_3") (pintype "bidirectional"))
    )
    (net (code "96") (name "unconnected-(U$1-P10.4{slash}TA3.0{slash}C0.7-Pad24)") (class "Default")
      (node (ref "U$1") (pin "24") (pinfunction "P10.4/TA3.0/C0.7_24") (pintype "bidirectional"))
    )
    (net (code "97") (name "unconnected-(U$1-P10.5{slash}TA3.1{slash}C0.6-Pad25)") (class "Default")
      (node (ref "U$1") (pin "25") (pinfunction "P10.5/TA3.1/C0.6_25") (pintype "bidirectional"))
    )
    (net (code "98") (name "unconnected-(U$1-PJ.2{slash}HFXOUT-Pad85)") (class "Default")
      (node (ref "U$1") (pin "85") (pinfunction "PJ.2/HFXOUT_85") (pintype "bidirectional"))
    )
    (net (code "99") (name "unconnected-(U$1-PJ.3{slash}HFXIN-Pad86)") (class "Default")
      (node (ref "U$1") (pin "86") (pinfunction "PJ.3/HFXIN_86") (pintype "bidirectional"))
    )
    (net (code "100") (name "unconnected-(U$3-PadP$3)") (class "Default")
      (node (ref "U$3") (pin "P$3") (pinfunction "P$3_P$3") (pintype "passive"))
    )
  )
)
